# CAN-POWER-B2B.net
KiCad netlist of a schematic drawn in Altium Designer
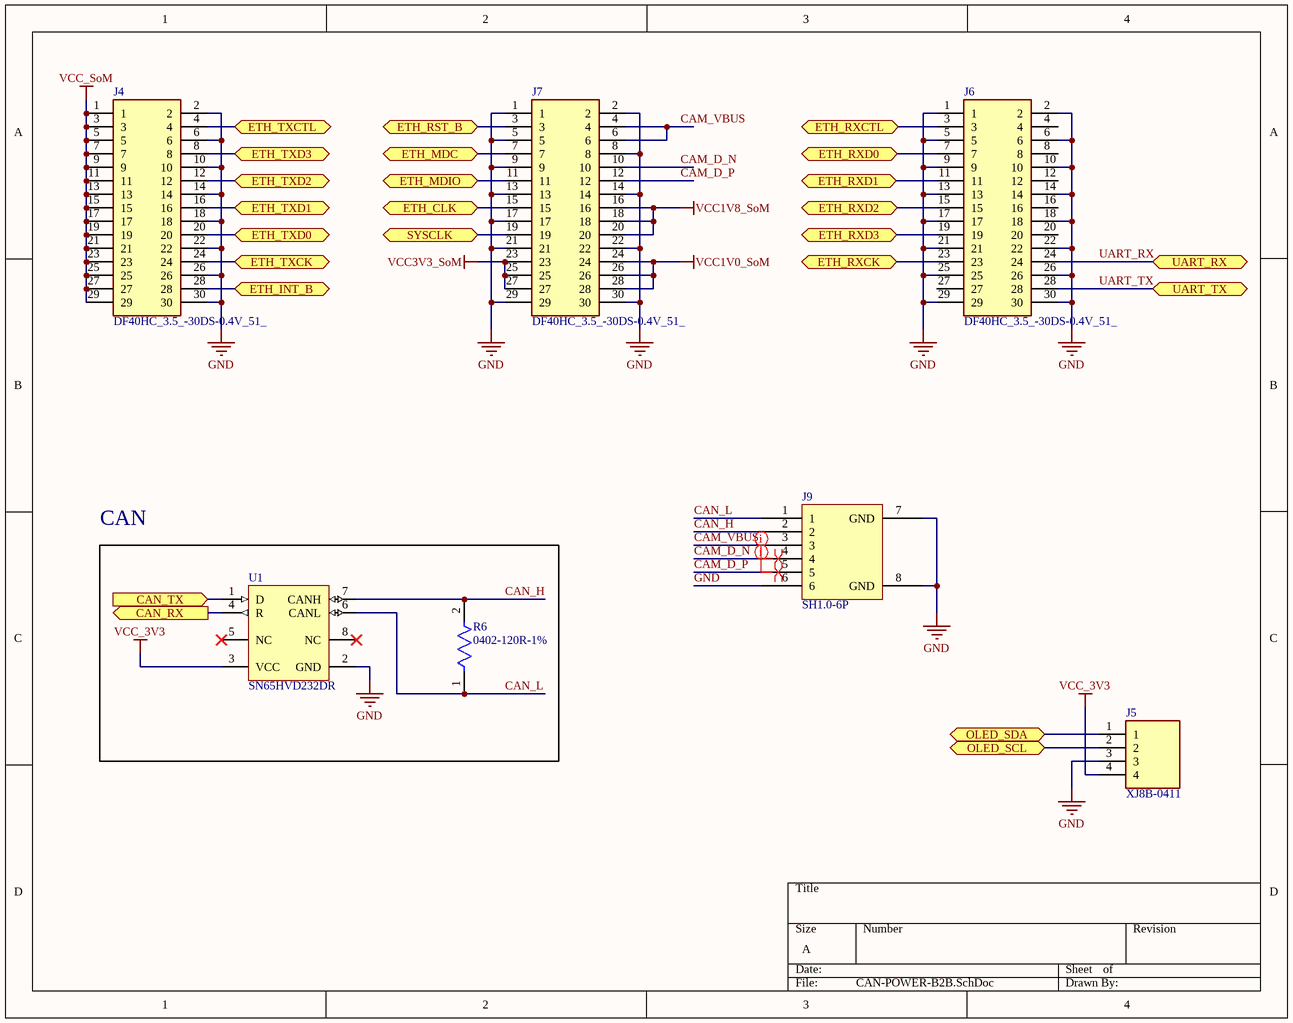
[diagram p0: CAN-POWER-B2B.SchDoc]

(export (version "E")
  (design (tool "Eeschema 10.0.6"))
  (components
    (comp (ref "J4")
      (value "DF40HC_3.5_-30DS-0.4V_51_")
      (footprint "SamacSys:DF40HC3530DS04V51")
      (description "Connector")
      (fields
        (field (name "MANUFACTURER_PART_NUMBER") "DF40HC(3.5)-30DS-0.4V(51)")
        (field (name "MOUSER PART NUMBER") "798-DF40HC3530DS04V")
      )
      (libsource (lib "*") (part "DF40HC_3.5_-30DS-0.4V_51_"))
    )
    (comp (ref "J5")
      (value "XJ8B-0411")
      (footprint "SamacSys:HDRV4W64P0X254_1X4_1020X250X580P")
      (description "Connector")
      (fields (field (name "MOUSER PART NUMBER") "653-XJ8B0411"))
      (libsource (lib "*") (part "XJ8B-0411"))
    )
    (comp (ref "J6")
      (value "DF40HC_3.5_-30DS-0.4V_51_")
      (footprint "SamacSys:DF40HC3530DS04V51")
      (description "Connector")
      (fields
        (field (name "MANUFACTURER_PART_NUMBER") "DF40HC(3.5)-30DS-0.4V(51)")
        (field (name "MOUSER PART NUMBER") "798-DF40HC3530DS04V")
      )
      (libsource (lib "*") (part "DF40HC_3.5_-30DS-0.4V_51_"))
    )
    (comp (ref "J7")
      (value "DF40HC_3.5_-30DS-0.4V_51_")
      (footprint "SamacSys:DF40HC3530DS04V51")
      (description "Connector")
      (fields
        (field (name "MANUFACTURER_PART_NUMBER") "DF40HC(3.5)-30DS-0.4V(51)")
        (field (name "MOUSER PART NUMBER") "798-DF40HC3530DS04V")
      )
      (libsource (lib "*") (part "DF40HC_3.5_-30DS-0.4V_51_"))
    )
    (comp (ref "J9") (value "SH1.0-6P") (footprint "SH1.0-6P") (libsource (lib "Schlib1") (part "SH1.0-6P")))
    (comp (ref "R6")
      (value "0402-120R-1%")
      (footprint "FP-CRCW0402-e3-IPC_C")
      (description "RES Thick Film, 0Ω, 0.063W, 0402")
      (fields (field (name "TOLERANCE") "5%"))
      (libsource (lib "Altium Content Vault") (part "1029c3af85768c4190bb7ad29bc67b5"))
    )
    (comp (ref "U1")
      (value "SN65HVD232DR")
      (footprint "D0008A_M")
      (description "3.3 V Can Transceiver, 17 mA, -40 to 85 degC, 8-pin SOIC (D), Green (RoHS & no Sb/Br)")
      (fields (field (name "MANUFACTURER") "Texas Instruments"))
      (libsource (lib "Altium Content Vault") (part "TI-SN65HVD232-SOIC_D-8"))
    )
  )
  (nets
    (net (code "1") (name "/CAM_D_N") (class "Default")
      (node (ref "J7") (pin "10") (pinfunction "10_10") (pintype "passive"))
      (node (ref "J9") (pin "4") (pinfunction "4_4") (pintype "passive"))
    )
    (net (code "2") (name "/CAM_D_P") (class "Default")
      (node (ref "J7") (pin "12") (pinfunction "12_12") (pintype "passive"))
      (node (ref "J9") (pin "5") (pinfunction "5_5") (pintype "passive"))
    )
    (net (code "3") (name "/CAM_VBUS") (class "Default")
      (node (ref "J7") (pin "4") (pinfunction "4_4") (pintype "passive"))
      (node (ref "J7") (pin "6") (pinfunction "6_6") (pintype "passive"))
      (node (ref "J9") (pin "3") (pinfunction "3_3") (pintype "passive"))
    )
    (net (code "4") (name "/CAN_H") (class "Default")
      (node (ref "J9") (pin "2") (pinfunction "2_2") (pintype "passive"))
      (node (ref "R6") (pin "2") (pinfunction "2_2") (pintype "passive"))
      (node (ref "U1") (pin "7") (pinfunction "CANH_7") (pintype "bidirectional"))
    )
    (net (code "5") (name "/CAN_L") (class "Default")
      (node (ref "J9") (pin "1") (pinfunction "1_1") (pintype "passive"))
      (node (ref "R6") (pin "1") (pinfunction "1_1") (pintype "passive"))
      (node (ref "U1") (pin "6") (pinfunction "CANL_6") (pintype "bidirectional"))
    )
    (net (code "6") (name "/CAN_RX") (class "Default")
      (node (ref "U1") (pin "4") (pinfunction "R_4") (pintype "output"))
    )
    (net (code "7") (name "/CAN_TX") (class "Default")
      (node (ref "U1") (pin "1") (pinfunction "D_1") (pintype "input"))
    )
    (net (code "8") (name "/ETH_CLK") (class "Default")
      (node (ref "J7") (pin "15") (pinfunction "15_15") (pintype "passive"))
    )
    (net (code "9") (name "/ETH_INT_B") (class "Default")
      (node (ref "J4") (pin "28") (pinfunction "28_28") (pintype "passive"))
    )
    (net (code "10") (name "/ETH_MDC") (class "Default")
      (node (ref "J7") (pin "7") (pinfunction "7_7") (pintype "passive"))
    )
    (net (code "11") (name "/ETH_MDIO") (class "Default")
      (node (ref "J7") (pin "11") (pinfunction "11_11") (pintype "passive"))
    )
    (net (code "12") (name "/ETH_RST_B") (class "Default")
      (node (ref "J7") (pin "3") (pinfunction "3_3") (pintype "passive"))
    )
    (net (code "13") (name "/ETH_RXCK") (class "Default")
      (node (ref "J6") (pin "23") (pinfunction "23_23") (pintype "passive"))
    )
    (net (code "14") (name "/ETH_RXCTL") (class "Default")
      (node (ref "J6") (pin "3") (pinfunction "3_3") (pintype "passive"))
    )
    (net (code "15") (name "/ETH_RXD0") (class "Default")
      (node (ref "J6") (pin "7") (pinfunction "7_7") (pintype "passive"))
    )
    (net (code "16") (name "/ETH_RXD1") (class "Default")
      (node (ref "J6") (pin "11") (pinfunction "11_11") (pintype "passive"))
    )
    (net (code "17") (name "/ETH_RXD2") (class "Default")
      (node (ref "J6") (pin "15") (pinfunction "15_15") (pintype "passive"))
    )
    (net (code "18") (name "/ETH_RXD3") (class "Default")
      (node (ref "J6") (pin "19") (pinfunction "19_19") (pintype "passive"))
    )
    (net (code "19") (name "/ETH_TXCK") (class "Default")
      (node (ref "J4") (pin "24") (pinfunction "24_24") (pintype "passive"))
    )
    (net (code "20") (name "/ETH_TXCTL") (class "Default")
      (node (ref "J4") (pin "4") (pinfunction "4_4") (pintype "passive"))
    )
    (net (code "21") (name "/ETH_TXD0") (class "Default")
      (node (ref "J4") (pin "20") (pinfunction "20_20") (pintype "passive"))
    )
    (net (code "22") (name "/ETH_TXD1") (class "Default")
      (node (ref "J4") (pin "16") (pinfunction "16_16") (pintype "passive"))
    )
    (net (code "23") (name "/ETH_TXD2") (class "Default")
      (node (ref "J4") (pin "12") (pinfunction "12_12") (pintype "passive"))
    )
    (net (code "24") (name "/ETH_TXD3") (class "Default")
      (node (ref "J4") (pin "8") (pinfunction "8_8") (pintype "passive"))
    )
    (net (code "25") (name "/OLED_SCL") (class "Default")
      (node (ref "J5") (pin "2") (pinfunction "2_2") (pintype "passive"))
    )
    (net (code "26") (name "/OLED_SDA") (class "Default")
      (node (ref "J5") (pin "1") (pinfunction "1_1") (pintype "passive"))
    )
    (net (code "27") (name "/SYSCLK") (class "Default")
      (node (ref "J7") (pin "19") (pinfunction "19_19") (pintype "passive"))
    )
    (net (code "28") (name "/UART_RX") (class "Default")
      (node (ref "J6") (pin "24") (pinfunction "24_24") (pintype "passive"))
    )
    (net (code "29") (name "/UART_TX") (class "Default")
      (node (ref "J6") (pin "28") (pinfunction "28_28") (pintype "passive"))
    )
    (net (code "30") (name "GND") (class "Default")
      (node (ref "J4") (pin "10") (pinfunction "10_10") (pintype "passive"))
      (node (ref "J4") (pin "14") (pinfunction "14_14") (pintype "passive"))
      (node (ref "J4") (pin "18") (pinfunction "18_18") (pintype "passive"))
      (node (ref "J4") (pin "2") (pinfunction "2_2") (pintype "passive"))
      (node (ref "J4") (pin "22") (pinfunction "22_22") (pintype "passive"))
      (node (ref "J4") (pin "26") (pinfunction "26_26") (pintype "passive"))
      (node (ref "J4") (pin "30") (pinfunction "30_30") (pintype "passive"))
      (node (ref "J4") (pin "6") (pinfunction "6_6") (pintype "passive"))
      (node (ref "J5") (pin "3") (pinfunction "3_3") (pintype "passive"))
      (node (ref "J6") (pin "1") (pinfunction "1_1") (pintype "passive"))
      (node (ref "J6") (pin "10") (pinfunction "10_10") (pintype "passive"))
      (node (ref "J6") (pin "13") (pinfunction "13_13") (pintype "passive"))
      (node (ref "J6") (pin "14") (pinfunction "14_14") (pintype "passive"))
      (node (ref "J6") (pin "17") (pinfunction "17_17") (pintype "passive"))
      (node (ref "J6") (pin "18") (pinfunction "18_18") (pintype "passive"))
      (node (ref "J6") (pin "2") (pinfunction "2_2") (pintype "passive"))
      (node (ref "J6") (pin "21") (pinfunction "21_21") (pintype "passive"))
      (node (ref "J6") (pin "22") (pinfunction "22_22") (pintype "passive"))
      (node (ref "J6") (pin "25") (pinfunction "25_25") (pintype "passive"))
      (node (ref "J6") (pin "26") (pinfunction "26_26") (pintype "passive"))
      (node (ref "J6") (pin "29") (pinfunction "29_29") (pintype "passive"))
      (node (ref "J6") (pin "30") (pinfunction "30_30") (pintype "passive"))
      (node (ref "J6") (pin "5") (pinfunction "5_5") (pintype "passive"))
      (node (ref "J6") (pin "6") (pinfunction "6_6") (pintype "passive"))
      (node (ref "J6") (pin "9") (pinfunction "9_9") (pintype "passive"))
      (node (ref "J7") (pin "1") (pinfunction "1_1") (pintype "passive"))
      (node (ref "J7") (pin "13") (pinfunction "13_13") (pintype "passive"))
      (node (ref "J7") (pin "14") (pinfunction "14_14") (pintype "passive"))
      (node (ref "J7") (pin "17") (pinfunction "17_17") (pintype "passive"))
      (node (ref "J7") (pin "2") (pinfunction "2_2") (pintype "passive"))
      (node (ref "J7") (pin "21") (pinfunction "21_21") (pintype "passive"))
      (node (ref "J7") (pin "22") (pinfunction "22_22") (pintype "passive"))
      (node (ref "J7") (pin "29") (pinfunction "29_29") (pintype "passive"))
      (node (ref "J7") (pin "30") (pinfunction "30_30") (pintype "passive"))
      (node (ref "J7") (pin "5") (pinfunction "5_5") (pintype "passive"))
      (node (ref "J7") (pin "8") (pinfunction "8_8") (pintype "passive"))
      (node (ref "J7") (pin "9") (pinfunction "9_9") (pintype "passive"))
      (node (ref "J9") (pin "6") (pinfunction "6_6") (pintype "passive"))
      (node (ref "J9") (pin "7") (pinfunction "GND_7") (pintype "passive"))
      (node (ref "J9") (pin "8") (pinfunction "GND_8") (pintype "passive"))
      (node (ref "U1") (pin "2") (pinfunction "GND_2") (pintype "power_in"))
    )
    (net (code "31") (name "VCC1V0_SoM") (class "Default")
      (node (ref "J7") (pin "24") (pinfunction "24_24") (pintype "passive"))
      (node (ref "J7") (pin "26") (pinfunction "26_26") (pintype "passive"))
      (node (ref "J7") (pin "28") (pinfunction "28_28") (pintype "passive"))
    )
    (net (code "32") (name "VCC1V8_SoM") (class "Default")
      (node (ref "J7") (pin "16") (pinfunction "16_16") (pintype "passive"))
      (node (ref "J7") (pin "18") (pinfunction "18_18") (pintype "passive"))
      (node (ref "J7") (pin "20") (pinfunction "20_20") (pintype "passive"))
    )
    (net (code "33") (name "VCC3V3_SoM") (class "Default")
      (node (ref "J7") (pin "23") (pinfunction "23_23") (pintype "passive"))
      (node (ref "J7") (pin "25") (pinfunction "25_25") (pintype "passive"))
      (node (ref "J7") (pin "27") (pinfunction "27_27") (pintype "passive"))
    )
    (net (code "34") (name "VCC_3V3") (class "Default")
      (node (ref "J5") (pin "4") (pinfunction "4_4") (pintype "passive"))
      (node (ref "U1") (pin "3") (pinfunction "VCC_3") (pintype "power_in"))
    )
    (net (code "35") (name "VCC_SoM") (class "Default")
      (node (ref "J4") (pin "1") (pinfunction "1_1") (pintype "passive"))
      (node (ref "J4") (pin "11") (pinfunction "11_11") (pintype "passive"))
      (node (ref "J4") (pin "13") (pinfunction "13_13") (pintype "passive"))
      (node (ref "J4") (pin "15") (pinfunction "15_15") (pintype "passive"))
      (node (ref "J4") (pin "17") (pinfunction "17_17") (pintype "passive"))
      (node (ref "J4") (pin "19") (pinfunction "19_19") (pintype "passive"))
      (node (ref "J4") (pin "21") (pinfunction "21_21") (pintype "passive"))
      (node (ref "J4") (pin "23") (pinfunction "23_23") (pintype "passive"))
      (node (ref "J4") (pin "25") (pinfunction "25_25") (pintype "passive"))
      (node (ref "J4") (pin "27") (pinfunction "27_27") (pintype "passive"))
      (node (ref "J4") (pin "29") (pinfunction "29_29") (pintype "passive"))
      (node (ref "J4") (pin "3") (pinfunction "3_3") (pintype "passive"))
      (node (ref "J4") (pin "5") (pinfunction "5_5") (pintype "passive"))
      (node (ref "J4") (pin "7") (pinfunction "7_7") (pintype "passive"))
      (node (ref "J4") (pin "9") (pinfunction "9_9") (pintype "passive"))
    )
    (net (code "36") (name "unconnected-(J6-Pad4)") (class "Default")
      (node (ref "J6") (pin "4") (pinfunction "4_4") (pintype "passive"))
    )
    (net (code "37") (name "unconnected-(J6-Pad8)") (class "Default")
      (node (ref "J6") (pin "8") (pinfunction "8_8") (pintype "passive"))
    )
    (net (code "38") (name "unconnected-(J6-Pad12)") (class "Default")
      (node (ref "J6") (pin "12") (pinfunction "12_12") (pintype "passive"))
    )
    (net (code "39") (name "unconnected-(J6-Pad16)") (class "Default")
      (node (ref "J6") (pin "16") (pinfunction "16_16") (pintype "passive"))
    )
    (net (code "40") (name "unconnected-(J6-Pad20)") (class "Default")
      (node (ref "J6") (pin "20") (pinfunction "20_20") (pintype "passive"))
    )
    (net (code "41") (name "unconnected-(J6-Pad27)") (class "Default")
      (node (ref "J6") (pin "27") (pinfunction "27_27") (pintype "passive"))
    )
    (net (code "42") (name "unconnected-(U1-NC-Pad5)") (class "Default")
      (node (ref "U1") (pin "5") (pinfunction "NC_5") (pintype "passive+no_connect"))
    )
    (net (code "43") (name "unconnected-(U1-NC-Pad8)") (class "Default")
      (node (ref "U1") (pin "8") (pinfunction "NC_8") (pintype "passive+no_connect"))
    )
  )
)
